# Mega.net
KiCad netlist of a schematic drawn in EAGLE
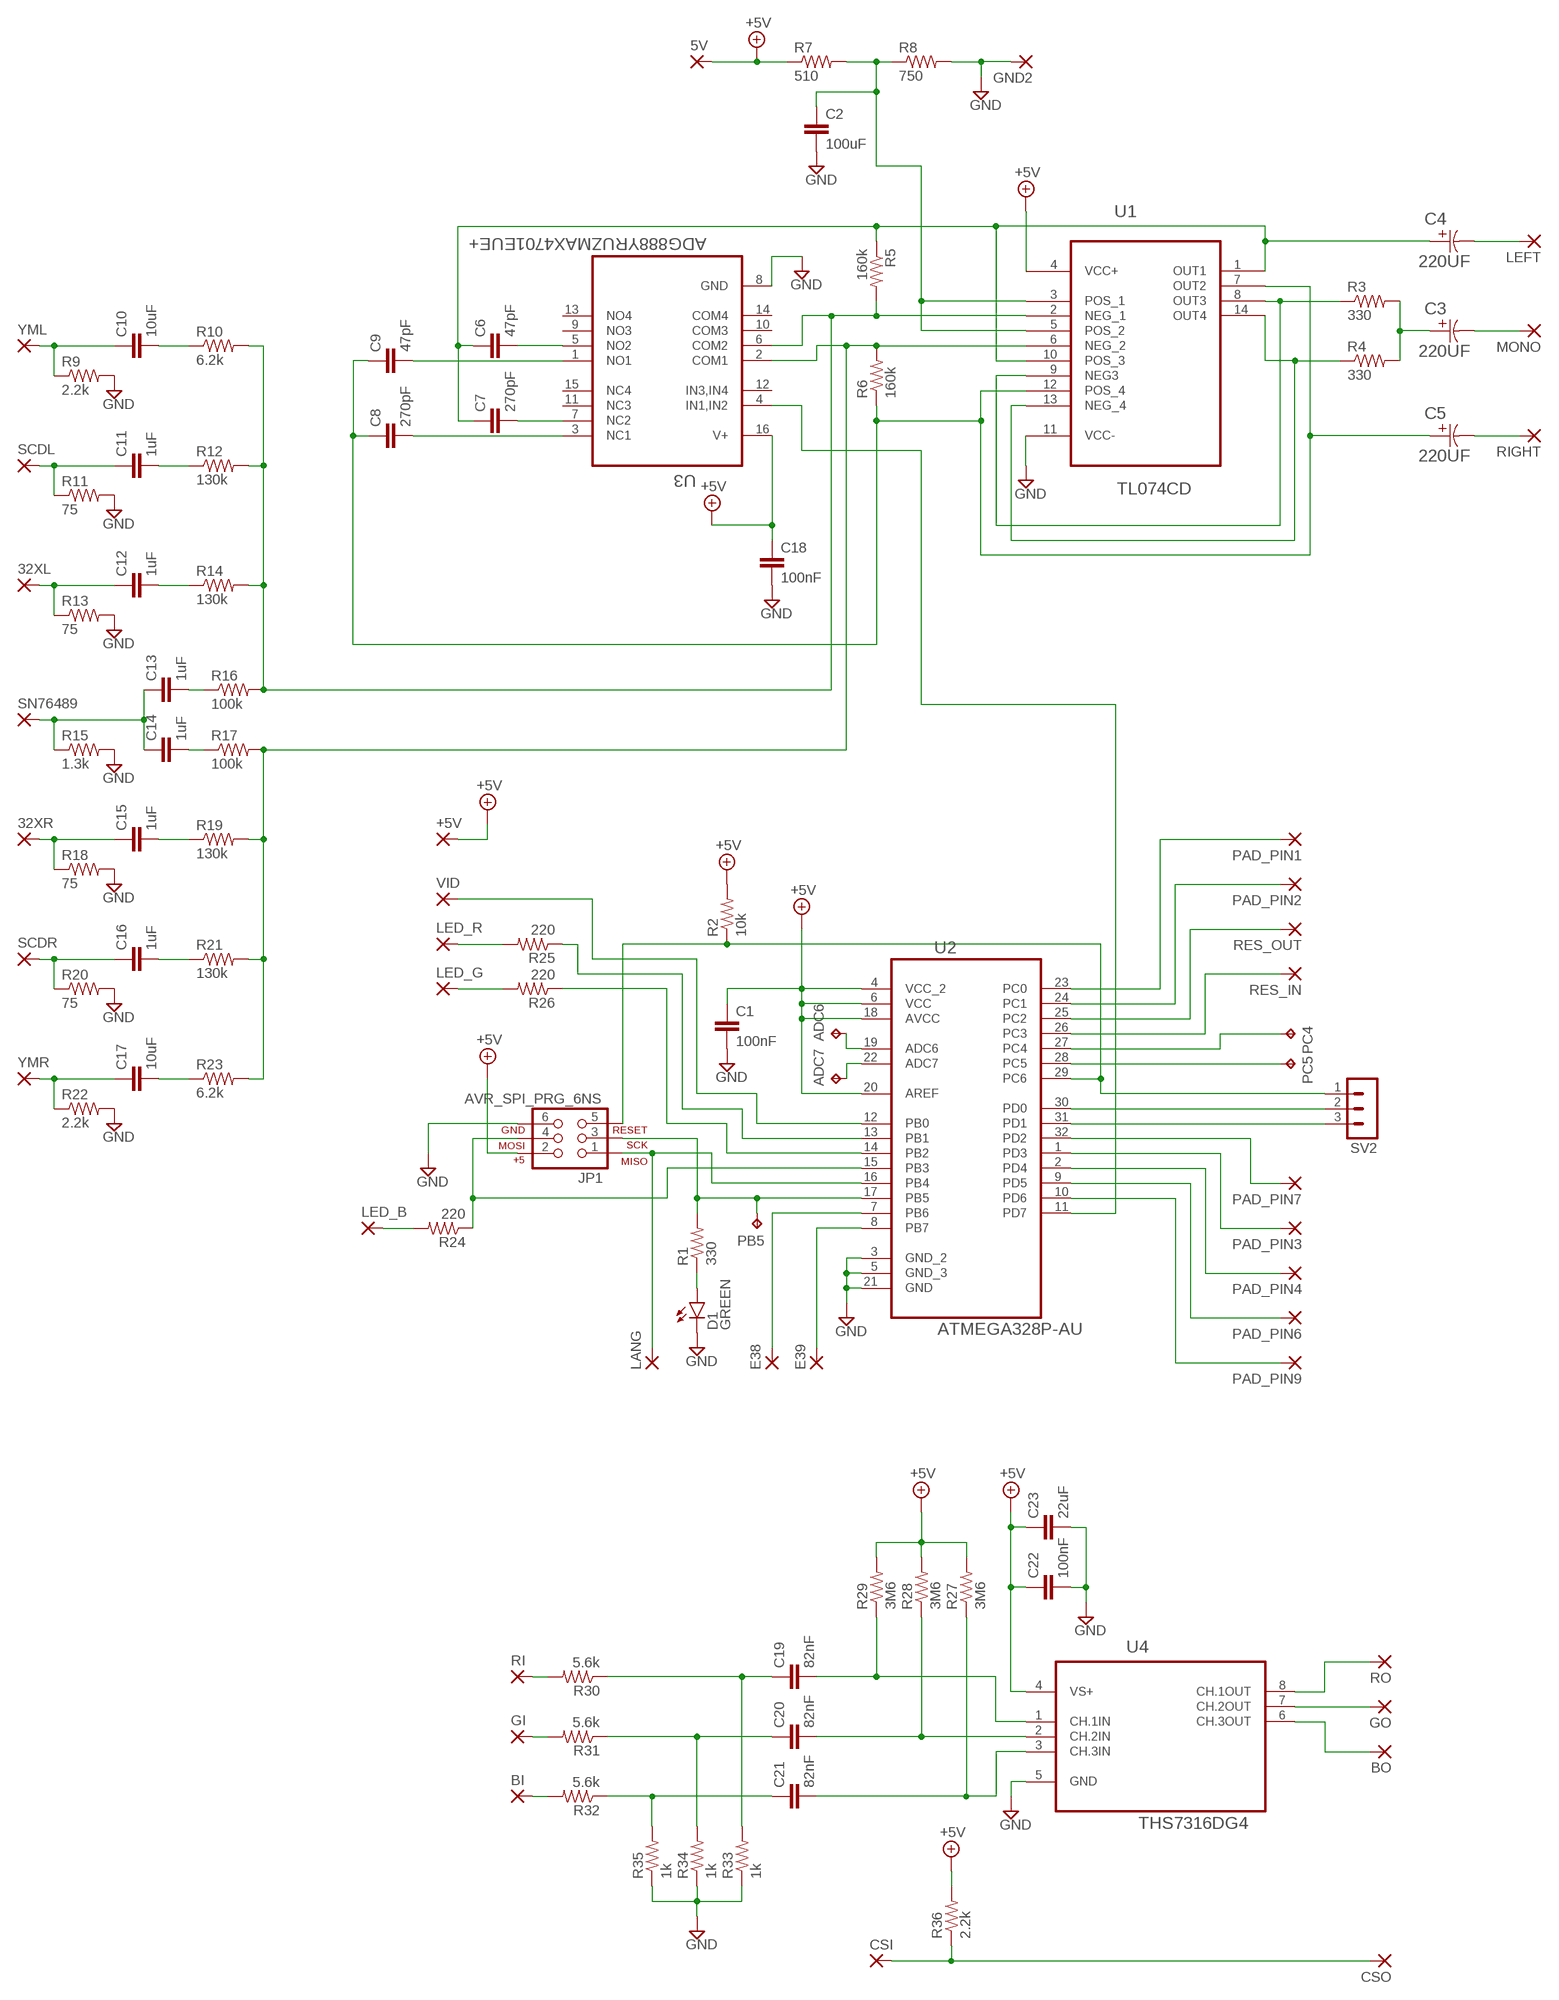
[diagram p0: schematic, sheet 1]

(export (version "E")
  (design (tool "Eeschema 10.0.6"))
  (components
    (comp (ref "+5V")
      (value "SMD2")
      (footprint "eagle-import:SMD1,27-2,54")
      (libsource (lib "eagle-import") (part "SMD2"))
    )
    (comp (ref "5V")
      (value "SMD2")
      (footprint "eagle-import:SMD1,27-2,54")
      (libsource (lib "eagle-import") (part "SMD2"))
    )
    (comp (ref "32XL")
      (value "SMD2")
      (footprint "eagle-import:SMD1,27-2,54")
      (libsource (lib "eagle-import") (part "SMD2"))
    )
    (comp (ref "32XR")
      (value "SMD2")
      (footprint "eagle-import:SMD1,27-2,54")
      (libsource (lib "eagle-import") (part "SMD2"))
    )
    (comp (ref "ADC6")
      (value "TPB1,27")
      (footprint "eagle-import:B1,27")
      (libsource (lib "eagle-import") (part "TPB1,27"))
    )
    (comp (ref "ADC7")
      (value "TPB1,27")
      (footprint "eagle-import:B1,27")
      (libsource (lib "eagle-import") (part "TPB1,27"))
    )
    (comp (ref "BI")
      (value "SMD2")
      (footprint "eagle-import:SMD1,27-2,54")
      (libsource (lib "eagle-import") (part "SMD2"))
    )
    (comp (ref "BO")
      (value "SMD2")
      (footprint "eagle-import:SMD1,27-2,54")
      (libsource (lib "eagle-import") (part "SMD2"))
    )
    (comp (ref "C1")
      (value "100nF")
      (footprint "eagle-import:0805")
      (libsource (lib "eagle-import") (part "CAP0805"))
    )
    (comp (ref "C2")
      (value "100uF")
      (footprint "eagle-import:1206")
      (libsource (lib "eagle-import") (part "CAP1206"))
    )
    (comp (ref "C3")
      (value "220UF")
      (footprint "eagle-import:CAPAE830X650N")
      (fields
        (field (name "MPN") "EEE-FK1C221P")
        (field (name "TOLERANCE") "±20 %")
        (field (name "TOLERANCE_1") "20 %")
      )
      (libsource (lib "eagle-import") (part "EEE--CASE-EFK1C221P"))
    )
    (comp (ref "C4")
      (value "220UF")
      (footprint "eagle-import:CAPAE830X650N")
      (fields
        (field (name "MPN") "EEE-FK1C221P")
        (field (name "TOLERANCE") "±20 %")
        (field (name "TOLERANCE_1") "20 %")
      )
      (libsource (lib "eagle-import") (part "EEE--CASE-EFK1C221P"))
    )
    (comp (ref "C5")
      (value "220UF")
      (footprint "eagle-import:CAPAE830X650N")
      (fields
        (field (name "MPN") "EEE-FK1C221P")
        (field (name "TOLERANCE") "±20 %")
        (field (name "TOLERANCE_1") "20 %")
      )
      (libsource (lib "eagle-import") (part "EEE--CASE-EFK1C221P"))
    )
    (comp (ref "C6")
      (value "47pF")
      (footprint "eagle-import:0805")
      (libsource (lib "eagle-import") (part "CAP0805"))
    )
    (comp (ref "C7")
      (value "270pF")
      (footprint "eagle-import:0805")
      (libsource (lib "eagle-import") (part "CAP0805"))
    )
    (comp (ref "C8")
      (value "270pF")
      (footprint "eagle-import:0805")
      (libsource (lib "eagle-import") (part "CAP0805"))
    )
    (comp (ref "C9")
      (value "47pF")
      (footprint "eagle-import:0805")
      (libsource (lib "eagle-import") (part "CAP0805"))
    )
    (comp (ref "C10")
      (value "10uF")
      (footprint "eagle-import:0805")
      (libsource (lib "eagle-import") (part "CAP0805"))
    )
    (comp (ref "C11")
      (value "1uF")
      (footprint "eagle-import:0805")
      (libsource (lib "eagle-import") (part "CAP0805"))
    )
    (comp (ref "C12")
      (value "1uF")
      (footprint "eagle-import:0805")
      (libsource (lib "eagle-import") (part "CAP0805"))
    )
    (comp (ref "C13")
      (value "1uF")
      (footprint "eagle-import:0805")
      (libsource (lib "eagle-import") (part "CAP0805"))
    )
    (comp (ref "C14")
      (value "1uF")
      (footprint "eagle-import:0805")
      (libsource (lib "eagle-import") (part "CAP0805"))
    )
    (comp (ref "C15")
      (value "1uF")
      (footprint "eagle-import:0805")
      (libsource (lib "eagle-import") (part "CAP0805"))
    )
    (comp (ref "C16")
      (value "1uF")
      (footprint "eagle-import:0805")
      (libsource (lib "eagle-import") (part "CAP0805"))
    )
    (comp (ref "C17")
      (value "10uF")
      (footprint "eagle-import:0805")
      (libsource (lib "eagle-import") (part "CAP0805"))
    )
    (comp (ref "C18")
      (value "100nF")
      (footprint "eagle-import:0805")
      (libsource (lib "eagle-import") (part "CAP0805"))
    )
    (comp (ref "C19")
      (value "82nF")
      (footprint "eagle-import:0805")
      (libsource (lib "eagle-import") (part "CAP0805"))
    )
    (comp (ref "C20")
      (value "82nF")
      (footprint "eagle-import:0805")
      (libsource (lib "eagle-import") (part "CAP0805"))
    )
    (comp (ref "C21")
      (value "82nF")
      (footprint "eagle-import:0805")
      (libsource (lib "eagle-import") (part "CAP0805"))
    )
    (comp (ref "C22")
      (value "100nF")
      (footprint "eagle-import:0805")
      (libsource (lib "eagle-import") (part "CAP0805"))
    )
    (comp (ref "C23")
      (value "22uF")
      (footprint "eagle-import:0805")
      (libsource (lib "eagle-import") (part "CAP0805"))
    )
    (comp (ref "CSI")
      (value "SMD2")
      (footprint "eagle-import:SMD1,27-2,54")
      (libsource (lib "eagle-import") (part "SMD2"))
    )
    (comp (ref "CSO")
      (value "SMD2")
      (footprint "eagle-import:SMD1,27-2,54")
      (libsource (lib "eagle-import") (part "SMD2"))
    )
    (comp (ref "D1")
      (value "GREEN")
      (footprint "eagle-import:LED-1206")
      (libsource (lib "eagle-import") (part "LED1206"))
    )
    (comp (ref "E38")
      (value "SMD2")
      (footprint "eagle-import:SMD1,27-2,54")
      (libsource (lib "eagle-import") (part "SMD2"))
    )
    (comp (ref "E39")
      (value "SMD2")
      (footprint "eagle-import:SMD1,27-2,54")
      (libsource (lib "eagle-import") (part "SMD2"))
    )
    (comp (ref "GI")
      (value "SMD2")
      (footprint "eagle-import:SMD1,27-2,54")
      (libsource (lib "eagle-import") (part "SMD2"))
    )
    (comp (ref "GND2")
      (value "SMD2")
      (footprint "eagle-import:SMD1,27-2,54")
      (libsource (lib "eagle-import") (part "SMD2"))
    )
    (comp (ref "GO")
      (value "SMD2")
      (footprint "eagle-import:SMD1,27-2,54")
      (libsource (lib "eagle-import") (part "SMD2"))
    )
    (comp (ref "JP1")
      (value "AVR_SPI_PRG_6NS")
      (footprint "eagle-import:2X3-NS")
      (libsource (lib "eagle-import") (part "AVR_SPI_PRG_6NS"))
    )
    (comp (ref "LANG")
      (value "SMD2")
      (footprint "eagle-import:SMD1,27-2,54")
      (libsource (lib "eagle-import") (part "SMD2"))
    )
    (comp (ref "LED_B")
      (value "SMD2")
      (footprint "eagle-import:SMD1,27-2,54")
      (libsource (lib "eagle-import") (part "SMD2"))
    )
    (comp (ref "LED_G")
      (value "SMD2")
      (footprint "eagle-import:SMD1,27-2,54")
      (libsource (lib "eagle-import") (part "SMD2"))
    )
    (comp (ref "LED_R")
      (value "SMD2")
      (footprint "eagle-import:SMD1,27-2,54")
      (libsource (lib "eagle-import") (part "SMD2"))
    )
    (comp (ref "LEFT")
      (value "SMD2")
      (footprint "eagle-import:SMD1,27-2,54")
      (libsource (lib "eagle-import") (part "SMD2"))
    )
    (comp (ref "MONO")
      (value "SMD2")
      (footprint "eagle-import:SMD1,27-2,54")
      (libsource (lib "eagle-import") (part "SMD2"))
    )
    (comp (ref "PAD_PIN1")
      (value "SMD2")
      (footprint "eagle-import:SMD1,27-2,54")
      (libsource (lib "eagle-import") (part "SMD2"))
    )
    (comp (ref "PAD_PIN2")
      (value "SMD2")
      (footprint "eagle-import:SMD1,27-2,54")
      (libsource (lib "eagle-import") (part "SMD2"))
    )
    (comp (ref "PAD_PIN3")
      (value "SMD2")
      (footprint "eagle-import:SMD1,27-2,54")
      (libsource (lib "eagle-import") (part "SMD2"))
    )
    (comp (ref "PAD_PIN4")
      (value "SMD2")
      (footprint "eagle-import:SMD1,27-2,54")
      (libsource (lib "eagle-import") (part "SMD2"))
    )
    (comp (ref "PAD_PIN6")
      (value "SMD2")
      (footprint "eagle-import:SMD1,27-2,54")
      (libsource (lib "eagle-import") (part "SMD2"))
    )
    (comp (ref "PAD_PIN7")
      (value "SMD2")
      (footprint "eagle-import:SMD1,27-2,54")
      (libsource (lib "eagle-import") (part "SMD2"))
    )
    (comp (ref "PAD_PIN9")
      (value "SMD2")
      (footprint "eagle-import:SMD1,27-2,54")
      (libsource (lib "eagle-import") (part "SMD2"))
    )
    (comp (ref "PB5")
      (value "TPB1,27")
      (footprint "eagle-import:B1,27")
      (libsource (lib "eagle-import") (part "TPB1,27"))
    )
    (comp (ref "PC4")
      (value "TPB1,27")
      (footprint "eagle-import:B1,27")
      (libsource (lib "eagle-import") (part "TPB1,27"))
    )
    (comp (ref "PC5")
      (value "TPB1,27")
      (footprint "eagle-import:B1,27")
      (libsource (lib "eagle-import") (part "TPB1,27"))
    )
    (comp (ref "R1")
      (value "330")
      (footprint "eagle-import:0805")
      (libsource (lib "eagle-import") (part "RESISTOR0805-RES"))
    )
    (comp (ref "R2")
      (value "10k")
      (footprint "eagle-import:0805")
      (libsource (lib "eagle-import") (part "RESISTOR0805-RES"))
    )
    (comp (ref "R3")
      (value "330")
      (footprint "eagle-import:0805")
      (libsource (lib "eagle-import") (part "RESISTOR0805-RES"))
    )
    (comp (ref "R4")
      (value "330")
      (footprint "eagle-import:0805")
      (libsource (lib "eagle-import") (part "RESISTOR0805-RES"))
    )
    (comp (ref "R5")
      (value "160k")
      (footprint "eagle-import:0805")
      (libsource (lib "eagle-import") (part "RESISTOR0805-RES"))
    )
    (comp (ref "R6")
      (value "160k")
      (footprint "eagle-import:0805")
      (libsource (lib "eagle-import") (part "RESISTOR0805-RES"))
    )
    (comp (ref "R7")
      (value "510")
      (footprint "eagle-import:0805")
      (libsource (lib "eagle-import") (part "RESISTOR0805-RES"))
    )
    (comp (ref "R8")
      (value "750")
      (footprint "eagle-import:0805")
      (libsource (lib "eagle-import") (part "RESISTOR0805-RES"))
    )
    (comp (ref "R9")
      (value "2.2k")
      (footprint "eagle-import:0805")
      (libsource (lib "eagle-import") (part "RESISTOR0805-RES"))
    )
    (comp (ref "R10")
      (value "6.2k")
      (footprint "eagle-import:0805")
      (libsource (lib "eagle-import") (part "RESISTOR0805-RES"))
    )
    (comp (ref "R11")
      (value "75")
      (footprint "eagle-import:0805")
      (libsource (lib "eagle-import") (part "RESISTOR0805-RES"))
    )
    (comp (ref "R12")
      (value "130k")
      (footprint "eagle-import:0805")
      (libsource (lib "eagle-import") (part "RESISTOR0805-RES"))
    )
    (comp (ref "R13")
      (value "75")
      (footprint "eagle-import:0805")
      (libsource (lib "eagle-import") (part "RESISTOR0805-RES"))
    )
    (comp (ref "R14")
      (value "130k")
      (footprint "eagle-import:0805")
      (libsource (lib "eagle-import") (part "RESISTOR0805-RES"))
    )
    (comp (ref "R15")
      (value "1.3k")
      (footprint "eagle-import:0805")
      (libsource (lib "eagle-import") (part "RESISTOR0805-RES"))
    )
    (comp (ref "R16")
      (value "100k")
      (footprint "eagle-import:0805")
      (libsource (lib "eagle-import") (part "RESISTOR0805-RES"))
    )
    (comp (ref "R17")
      (value "100k")
      (footprint "eagle-import:0805")
      (libsource (lib "eagle-import") (part "RESISTOR0805-RES"))
    )
    (comp (ref "R18")
      (value "75")
      (footprint "eagle-import:0805")
      (libsource (lib "eagle-import") (part "RESISTOR0805-RES"))
    )
    (comp (ref "R19")
      (value "130k")
      (footprint "eagle-import:0805")
      (libsource (lib "eagle-import") (part "RESISTOR0805-RES"))
    )
    (comp (ref "R20")
      (value "75")
      (footprint "eagle-import:0805")
      (libsource (lib "eagle-import") (part "RESISTOR0805-RES"))
    )
    (comp (ref "R21")
      (value "130k")
      (footprint "eagle-import:0805")
      (libsource (lib "eagle-import") (part "RESISTOR0805-RES"))
    )
    (comp (ref "R22")
      (value "2.2k")
      (footprint "eagle-import:0805")
      (libsource (lib "eagle-import") (part "RESISTOR0805-RES"))
    )
    (comp (ref "R23")
      (value "6.2k")
      (footprint "eagle-import:0805")
      (libsource (lib "eagle-import") (part "RESISTOR0805-RES"))
    )
    (comp (ref "R24")
      (value "220")
      (footprint "eagle-import:0805")
      (libsource (lib "eagle-import") (part "RESISTOR0805-RES"))
    )
    (comp (ref "R25")
      (value "220")
      (footprint "eagle-import:0805")
      (libsource (lib "eagle-import") (part "RESISTOR0805-RES"))
    )
    (comp (ref "R26")
      (value "220")
      (footprint "eagle-import:0805")
      (libsource (lib "eagle-import") (part "RESISTOR0805-RES"))
    )
    (comp (ref "R27")
      (value "3M6")
      (footprint "eagle-import:0805")
      (libsource (lib "eagle-import") (part "RESISTOR0805-RES"))
    )
    (comp (ref "R28")
      (value "3M6")
      (footprint "eagle-import:0805")
      (libsource (lib "eagle-import") (part "RESISTOR0805-RES"))
    )
    (comp (ref "R29")
      (value "3M6")
      (footprint "eagle-import:0805")
      (libsource (lib "eagle-import") (part "RESISTOR0805-RES"))
    )
    (comp (ref "R30")
      (value "5.6k")
      (footprint "eagle-import:0805")
      (libsource (lib "eagle-import") (part "RESISTOR0805-RES"))
    )
    (comp (ref "R31")
      (value "5.6k")
      (footprint "eagle-import:0805")
      (libsource (lib "eagle-import") (part "RESISTOR0805-RES"))
    )
    (comp (ref "R32")
      (value "5.6k")
      (footprint "eagle-import:0805")
      (libsource (lib "eagle-import") (part "RESISTOR0805-RES"))
    )
    (comp (ref "R33")
      (value "1k")
      (footprint "eagle-import:0805")
      (libsource (lib "eagle-import") (part "RESISTOR0805-RES"))
    )
    (comp (ref "R34")
      (value "1k")
      (footprint "eagle-import:0805")
      (libsource (lib "eagle-import") (part "RESISTOR0805-RES"))
    )
    (comp (ref "R35")
      (value "1k")
      (footprint "eagle-import:0805")
      (libsource (lib "eagle-import") (part "RESISTOR0805-RES"))
    )
    (comp (ref "R36")
      (value "2.2k")
      (footprint "eagle-import:0805")
      (libsource (lib "eagle-import") (part "RESISTOR0805-RES"))
    )
    (comp (ref "RES_IN")
      (value "SMD2")
      (footprint "eagle-import:SMD1,27-2,54")
      (libsource (lib "eagle-import") (part "SMD2"))
    )
    (comp (ref "RES_OUT")
      (value "SMD2")
      (footprint "eagle-import:SMD1,27-2,54")
      (libsource (lib "eagle-import") (part "SMD2"))
    )
    (comp (ref "RI")
      (value "SMD2")
      (footprint "eagle-import:SMD1,27-2,54")
      (libsource (lib "eagle-import") (part "SMD2"))
    )
    (comp (ref "RIGHT")
      (value "SMD2")
      (footprint "eagle-import:SMD1,27-2,54")
      (libsource (lib "eagle-import") (part "SMD2"))
    )
    (comp (ref "RO")
      (value "SMD2")
      (footprint "eagle-import:SMD1,27-2,54")
      (libsource (lib "eagle-import") (part "SMD2"))
    )
    (comp (ref "SCDL")
      (value "SMD2")
      (footprint "eagle-import:SMD1,27-2,54")
      (libsource (lib "eagle-import") (part "SMD2"))
    )
    (comp (ref "SCDR")
      (value "SMD2")
      (footprint "eagle-import:SMD1,27-2,54")
      (libsource (lib "eagle-import") (part "SMD2"))
    )
    (comp (ref "SN76489")
      (value "SMD2")
      (footprint "eagle-import:SMD1,27-2,54")
      (libsource (lib "eagle-import") (part "SMD2"))
    )
    (comp (ref "SV2")
      (value "MA03-1")
      (footprint "eagle-import:MA03-1")
      (libsource (lib "eagle-import") (part "MA03-1"))
    )
    (comp (ref "U1")
      (value "TL074CD")
      (footprint "eagle-import:SOIC127P600X175-14N")
      (libsource (lib "eagle-import") (part "TL074CD"))
    )
    (comp (ref "U2")
      (value "ATMEGA328P-AU")
      (footprint "eagle-import:QFP80P900X900X120-32N")
      (libsource (lib "eagle-import") (part "ATMEGA328P-AU"))
    )
    (comp (ref "U3")
      (value "ADG888YRUZMAX4701EUE+")
      (footprint "eagle-import:SOP65P640X120-16N")
      (libsource (lib "eagle-import") (part "ADG888YRUZMAX4701EUE+"))
    )
    (comp (ref "U4")
      (value "THS7316DG4")
      (footprint "eagle-import:SOIC127P600X175-8N")
      (libsource (lib "eagle-import") (part "THS7316DG4"))
    )
    (comp (ref "VID")
      (value "SMD2")
      (footprint "eagle-import:SMD1,27-2,54")
      (libsource (lib "eagle-import") (part "SMD2"))
    )
    (comp (ref "YML")
      (value "SMD2")
      (footprint "eagle-import:SMD1,27-2,54")
      (libsource (lib "eagle-import") (part "SMD2"))
    )
    (comp (ref "YMR")
      (value "SMD2")
      (footprint "eagle-import:SMD1,27-2,54")
      (libsource (lib "eagle-import") (part "SMD2"))
    )
  )
  (nets
    (net (code "1") (name "+5V") (class "Default")
      (node (ref "+5V") (pin "1") (pinfunction "P_1") (pintype "passive"))
      (node (ref "5V") (pin "1") (pinfunction "P_1") (pintype "passive"))
      (node (ref "C1") (pin "1") (pinfunction "1_1") (pintype "passive"))
      (node (ref "C18") (pin "1") (pinfunction "1_1") (pintype "passive"))
      (node (ref "C22") (pin "1") (pinfunction "1_1") (pintype "passive"))
      (node (ref "C23") (pin "1") (pinfunction "1_1") (pintype "passive"))
      (node (ref "JP1") (pin "2") (pinfunction "2_2") (pintype "passive"))
      (node (ref "R2") (pin "2") (pinfunction "2_2") (pintype "passive"))
      (node (ref "R27") (pin "2") (pinfunction "2_2") (pintype "passive"))
      (node (ref "R28") (pin "2") (pinfunction "2_2") (pintype "passive"))
      (node (ref "R29") (pin "2") (pinfunction "2_2") (pintype "passive"))
      (node (ref "R36") (pin "2") (pinfunction "2_2") (pintype "passive"))
      (node (ref "R7") (pin "1") (pinfunction "1_1") (pintype "passive"))
      (node (ref "U1") (pin "4") (pinfunction "VCC+_4") (pintype "power_in"))
      (node (ref "U2") (pin "18") (pinfunction "AVCC_18") (pintype "power_in"))
      (node (ref "U2") (pin "20") (pinfunction "AREF_20") (pintype "input"))
      (node (ref "U2") (pin "4") (pinfunction "VCC_2_4") (pintype "power_in"))
      (node (ref "U2") (pin "6") (pinfunction "VCC_6") (pintype "power_in"))
      (node (ref "U3") (pin "16") (pinfunction "V+_16") (pintype "power_in"))
      (node (ref "U4") (pin "4") (pinfunction "VS+_4") (pintype "power_in"))
    )
    (net (code "2") (name "GND") (class "Default")
      (node (ref "C1") (pin "2") (pinfunction "2_2") (pintype "passive"))
      (node (ref "C18") (pin "2") (pinfunction "2_2") (pintype "passive"))
      (node (ref "C2") (pin "2") (pinfunction "2_2") (pintype "passive"))
      (node (ref "C22") (pin "2") (pinfunction "2_2") (pintype "passive"))
      (node (ref "C23") (pin "2") (pinfunction "2_2") (pintype "passive"))
      (node (ref "D1") (pin "C") (pinfunction "C_C") (pintype "passive"))
      (node (ref "GND2") (pin "1") (pinfunction "P_1") (pintype "passive"))
      (node (ref "JP1") (pin "6") (pinfunction "6_6") (pintype "passive"))
      (node (ref "R11") (pin "2") (pinfunction "2_2") (pintype "passive"))
      (node (ref "R13") (pin "2") (pinfunction "2_2") (pintype "passive"))
      (node (ref "R15") (pin "2") (pinfunction "2_2") (pintype "passive"))
      (node (ref "R18") (pin "2") (pinfunction "2_2") (pintype "passive"))
      (node (ref "R20") (pin "2") (pinfunction "2_2") (pintype "passive"))
      (node (ref "R22") (pin "2") (pinfunction "2_2") (pintype "passive"))
      (node (ref "R33") (pin "1") (pinfunction "1_1") (pintype "passive"))
      (node (ref "R34") (pin "1") (pinfunction "1_1") (pintype "passive"))
      (node (ref "R35") (pin "1") (pinfunction "1_1") (pintype "passive"))
      (node (ref "R8") (pin "2") (pinfunction "2_2") (pintype "passive"))
      (node (ref "R9") (pin "2") (pinfunction "2_2") (pintype "passive"))
      (node (ref "U1") (pin "11") (pinfunction "VCC-_11") (pintype "power_in"))
      (node (ref "U2") (pin "21") (pinfunction "GND_21") (pintype "passive"))
      (node (ref "U2") (pin "3") (pinfunction "GND_2_3") (pintype "passive"))
      (node (ref "U2") (pin "5") (pinfunction "GND_3_5") (pintype "passive"))
      (node (ref "U3") (pin "8") (pinfunction "GND_8") (pintype "passive"))
      (node (ref "U4") (pin "5") (pinfunction "GND_5") (pintype "passive"))
    )
    (net (code "3") (name "Net-(32XL-P)") (class "Default")
      (node (ref "32XL") (pin "1") (pinfunction "P_1") (pintype "passive"))
      (node (ref "C12") (pin "1") (pinfunction "1_1") (pintype "passive"))
      (node (ref "R13") (pin "1") (pinfunction "1_1") (pintype "passive"))
    )
    (net (code "4") (name "Net-(32XR-P)") (class "Default")
      (node (ref "32XR") (pin "1") (pinfunction "P_1") (pintype "passive"))
      (node (ref "C15") (pin "1") (pinfunction "1_1") (pintype "passive"))
      (node (ref "R18") (pin "1") (pinfunction "1_1") (pintype "passive"))
    )
    (net (code "5") (name "Net-(BI-P)") (class "Default")
      (node (ref "BI") (pin "1") (pinfunction "P_1") (pintype "passive"))
      (node (ref "R32") (pin "2") (pinfunction "2_2") (pintype "passive"))
    )
    (net (code "6") (name "Net-(BO-P)") (class "Default")
      (node (ref "BO") (pin "1") (pinfunction "P_1") (pintype "passive"))
      (node (ref "U4") (pin "6") (pinfunction "CH.3OUT_6") (pintype "output"))
    )
    (net (code "7") (name "Net-(C3-Pad1)") (class "Default")
      (node (ref "C3") (pin "1") (pinfunction "1_1") (pintype "passive"))
      (node (ref "R3") (pin "2") (pinfunction "2_2") (pintype "passive"))
      (node (ref "R4") (pin "2") (pinfunction "2_2") (pintype "passive"))
    )
    (net (code "8") (name "Net-(C10-Pad2)") (class "Default")
      (node (ref "C10") (pin "2") (pinfunction "2_2") (pintype "passive"))
      (node (ref "R10") (pin "1") (pinfunction "1_1") (pintype "passive"))
    )
    (net (code "9") (name "Net-(C11-Pad2)") (class "Default")
      (node (ref "C11") (pin "2") (pinfunction "2_2") (pintype "passive"))
      (node (ref "R12") (pin "1") (pinfunction "1_1") (pintype "passive"))
    )
    (net (code "10") (name "Net-(C12-Pad2)") (class "Default")
      (node (ref "C12") (pin "2") (pinfunction "2_2") (pintype "passive"))
      (node (ref "R14") (pin "1") (pinfunction "1_1") (pintype "passive"))
    )
    (net (code "11") (name "Net-(C13-Pad2)") (class "Default")
      (node (ref "C13") (pin "2") (pinfunction "2_2") (pintype "passive"))
      (node (ref "R16") (pin "1") (pinfunction "1_1") (pintype "passive"))
    )
    (net (code "12") (name "Net-(C14-Pad2)") (class "Default")
      (node (ref "C14") (pin "2") (pinfunction "2_2") (pintype "passive"))
      (node (ref "R17") (pin "1") (pinfunction "1_1") (pintype "passive"))
    )
    (net (code "13") (name "Net-(C15-Pad2)") (class "Default")
      (node (ref "C15") (pin "2") (pinfunction "2_2") (pintype "passive"))
      (node (ref "R19") (pin "1") (pinfunction "1_1") (pintype "passive"))
    )
    (net (code "14") (name "Net-(C16-Pad2)") (class "Default")
      (node (ref "C16") (pin "2") (pinfunction "2_2") (pintype "passive"))
      (node (ref "R21") (pin "1") (pinfunction "1_1") (pintype "passive"))
    )
    (net (code "15") (name "Net-(C17-Pad2)") (class "Default")
      (node (ref "C17") (pin "2") (pinfunction "2_2") (pintype "passive"))
      (node (ref "R23") (pin "1") (pinfunction "1_1") (pintype "passive"))
    )
    (net (code "16") (name "Net-(C19-Pad1)") (class "Default")
      (node (ref "C19") (pin "1") (pinfunction "1_1") (pintype "passive"))
      (node (ref "R30") (pin "1") (pinfunction "1_1") (pintype "passive"))
      (node (ref "R33") (pin "2") (pinfunction "2_2") (pintype "passive"))
    )
    (net (code "17") (name "Net-(C20-Pad1)") (class "Default")
      (node (ref "C20") (pin "1") (pinfunction "1_1") (pintype "passive"))
      (node (ref "R31") (pin "1") (pinfunction "1_1") (pintype "passive"))
      (node (ref "R34") (pin "2") (pinfunction "2_2") (pintype "passive"))
    )
    (net (code "18") (name "Net-(C21-Pad1)") (class "Default")
      (node (ref "C21") (pin "1") (pinfunction "1_1") (pintype "passive"))
      (node (ref "R32") (pin "1") (pinfunction "1_1") (pintype "passive"))
      (node (ref "R35") (pin "2") (pinfunction "2_2") (pintype "passive"))
    )
    (net (code "19") (name "Net-(CSI-P)") (class "Default")
      (node (ref "CSI") (pin "1") (pinfunction "P_1") (pintype "passive"))
      (node (ref "CSO") (pin "1") (pinfunction "P_1") (pintype "passive"))
      (node (ref "R36") (pin "1") (pinfunction "1_1") (pintype "passive"))
    )
    (net (code "20") (name "Net-(D1-PadA)") (class "Default")
      (node (ref "D1") (pin "A") (pinfunction "A_A") (pintype "passive"))
      (node (ref "R1") (pin "1") (pinfunction "1_1") (pintype "passive"))
    )
    (net (code "21") (name "Net-(E38-P)") (class "Default")
      (node (ref "E38") (pin "1") (pinfunction "P_1") (pintype "passive"))
      (node (ref "U2") (pin "7") (pinfunction "PB6_7") (pintype "bidirectional"))
    )
    (net (code "22") (name "Net-(E39-P)") (class "Default")
      (node (ref "E39") (pin "1") (pinfunction "P_1") (pintype "passive"))
      (node (ref "U2") (pin "8") (pinfunction "PB7_8") (pintype "bidirectional"))
    )
    (net (code "23") (name "Net-(GI-P)") (class "Default")
      (node (ref "GI") (pin "1") (pinfunction "P_1") (pintype "passive"))
      (node (ref "R31") (pin "2") (pinfunction "2_2") (pintype "passive"))
    )
    (net (code "24") (name "Net-(GO-P)") (class "Default")
      (node (ref "GO") (pin "1") (pinfunction "P_1") (pintype "passive"))
      (node (ref "U4") (pin "7") (pinfunction "CH.2OUT_7") (pintype "output"))
    )
    (net (code "25") (name "Net-(LANG-P)") (class "Default")
      (node (ref "JP1") (pin "1") (pinfunction "1_1") (pintype "passive"))
      (node (ref "LANG") (pin "1") (pinfunction "P_1") (pintype "passive"))
      (node (ref "U2") (pin "16") (pinfunction "PB4_16") (pintype "bidirectional"))
    )
    (net (code "26") (name "Net-(LED_B-P)") (class "Default")
      (node (ref "LED_B") (pin "1") (pinfunction "P_1") (pintype "passive"))
      (node (ref "R24") (pin "2") (pinfunction "2_2") (pintype "passive"))
    )
    (net (code "27") (name "Net-(LED_G-P)") (class "Default")
      (node (ref "LED_G") (pin "1") (pinfunction "P_1") (pintype "passive"))
      (node (ref "R26") (pin "2") (pinfunction "2_2") (pintype "passive"))
    )
    (net (code "28") (name "Net-(LED_R-P)") (class "Default")
      (node (ref "LED_R") (pin "1") (pinfunction "P_1") (pintype "passive"))
      (node (ref "R25") (pin "2") (pinfunction "2_2") (pintype "passive"))
    )
    (net (code "29") (name "Net-(LEFT-P)") (class "Default")
      (node (ref "C4") (pin "2") (pinfunction "2_2") (pintype "passive"))
      (node (ref "LEFT") (pin "1") (pinfunction "P_1") (pintype "passive"))
    )
    (net (code "30") (name "Net-(MONO-P)") (class "Default")
      (node (ref "C3") (pin "2") (pinfunction "2_2") (pintype "passive"))
      (node (ref "MONO") (pin "1") (pinfunction "P_1") (pintype "passive"))
    )
    (net (code "31") (name "Net-(PAD_PIN1-P)") (class "Default")
      (node (ref "PAD_PIN1") (pin "1") (pinfunction "P_1") (pintype "passive"))
      (node (ref "U2") (pin "23") (pinfunction "PC0_23") (pintype "bidirectional"))
    )
    (net (code "32") (name "Net-(PAD_PIN2-P)") (class "Default")
      (node (ref "PAD_PIN2") (pin "1") (pinfunction "P_1") (pintype "passive"))
      (node (ref "U2") (pin "24") (pinfunction "PC1_24") (pintype "bidirectional"))
    )
    (net (code "33") (name "Net-(PAD_PIN3-P)") (class "Default")
      (node (ref "PAD_PIN3") (pin "1") (pinfunction "P_1") (pintype "passive"))
      (node (ref "U2") (pin "1") (pinfunction "PD3_1") (pintype "bidirectional"))
    )
    (net (code "34") (name "Net-(PAD_PIN4-P)") (class "Default")
      (node (ref "PAD_PIN4") (pin "1") (pinfunction "P_1") (pintype "passive"))
      (node (ref "U2") (pin "2") (pinfunction "PD4_2") (pintype "bidirectional"))
    )
    (net (code "35") (name "Net-(PAD_PIN6-P)") (class "Default")
      (node (ref "PAD_PIN6") (pin "1") (pinfunction "P_1") (pintype "passive"))
      (node (ref "U2") (pin "9") (pinfunction "PD5_9") (pintype "bidirectional"))
    )
    (net (code "36") (name "Net-(PAD_PIN7-P)") (class "Default")
      (node (ref "PAD_PIN7") (pin "1") (pinfunction "P_1") (pintype "passive"))
      (node (ref "U2") (pin "32") (pinfunction "PD2_32") (pintype "bidirectional"))
    )
    (net (code "37") (name "Net-(PAD_PIN9-P)") (class "Default")
      (node (ref "PAD_PIN9") (pin "1") (pinfunction "P_1") (pintype "passive"))
      (node (ref "U2") (pin "10") (pinfunction "PD6_10") (pintype "bidirectional"))
    )
    (net (code "38") (name "Net-(RES_IN-P)") (class "Default")
      (node (ref "RES_IN") (pin "1") (pinfunction "P_1") (pintype "passive"))
      (node (ref "U2") (pin "26") (pinfunction "PC3_26") (pintype "bidirectional"))
    )
    (net (code "39") (name "Net-(RES_OUT-P)") (class "Default")
      (node (ref "RES_OUT") (pin "1") (pinfunction "P_1") (pintype "passive"))
      (node (ref "U2") (pin "25") (pinfunction "PC2_25") (pintype "bidirectional"))
    )
    (net (code "40") (name "Net-(RI-P)") (class "Default")
      (node (ref "R30") (pin "2") (pinfunction "2_2") (pintype "passive"))
      (node (ref "RI") (pin "1") (pinfunction "P_1") (pintype "passive"))
    )
    (net (code "41") (name "Net-(RIGHT-P)") (class "Default")
      (node (ref "C5") (pin "2") (pinfunction "2_2") (pintype "passive"))
      (node (ref "RIGHT") (pin "1") (pinfunction "P_1") (pintype "passive"))
    )
    (net (code "42") (name "Net-(RO-P)") (class "Default")
      (node (ref "RO") (pin "1") (pinfunction "P_1") (pintype "passive"))
      (node (ref "U4") (pin "8") (pinfunction "CH.1OUT_8") (pintype "output"))
    )
    (net (code "43") (name "Net-(SCDL-P)") (class "Default")
      (node (ref "C11") (pin "1") (pinfunction "1_1") (pintype "passive"))
      (node (ref "R11") (pin "1") (pinfunction "1_1") (pintype "passive"))
      (node (ref "SCDL") (pin "1") (pinfunction "P_1") (pintype "passive"))
    )
    (net (code "44") (name "Net-(SCDR-P)") (class "Default")
      (node (ref "C16") (pin "1") (pinfunction "1_1") (pintype "passive"))
      (node (ref "R20") (pin "1") (pinfunction "1_1") (pintype "passive"))
      (node (ref "SCDR") (pin "1") (pinfunction "P_1") (pintype "passive"))
    )
    (net (code "45") (name "Net-(SN76489-P)") (class "Default")
      (node (ref "C13") (pin "1") (pinfunction "1_1") (pintype "passive"))
      (node (ref "C14") (pin "1") (pinfunction "1_1") (pintype "passive"))
      (node (ref "R15") (pin "1") (pinfunction "1_1") (pintype "passive"))
      (node (ref "SN76489") (pin "1") (pinfunction "P_1") (pintype "passive"))
    )
    (net (code "46") (name "Net-(U1-NEG3)") (class "Default")
      (node (ref "R3") (pin "1") (pinfunction "1_1") (pintype "passive"))
      (node (ref "U1") (pin "8") (pinfunction "OUT3_8") (pintype "output"))
      (node (ref "U1") (pin "9") (pinfunction "NEG3_9") (pintype "input"))
    )
    (net (code "47") (name "Net-(U1-NEG_1)") (class "Default")
      (node (ref "R10") (pin "2") (pinfunction "2_2") (pintype "passive"))
      (node (ref "R12") (pin "2") (pinfunction "2_2") (pintype "passive"))
      (node (ref "R14") (pin "2") (pinfunction "2_2") (pintype "passive"))
      (node (ref "R16") (pin "2") (pinfunction "2_2") (pintype "passive"))
      (node (ref "R5") (pin "2") (pinfunction "2_2") (pintype "passive"))
      (node (ref "U1") (pin "2") (pinfunction "NEG_1_2") (pintype "input"))
      (node (ref "U3") (pin "6") (pinfunction "COM2_6") (pintype "bidirectional"))
    )
    (net (code "48") (name "Net-(U1-NEG_2)") (class "Default")
      (node (ref "R17") (pin "2") (pinfunction "2_2") (pintype "passive"))
      (node (ref "R19") (pin "2") (pinfunction "2_2") (pintype "passive"))
      (node (ref "R21") (pin "2") (pinfunction "2_2") (pintype "passive"))
      (node (ref "R23") (pin "2") (pinfunction "2_2") (pintype "passive"))
      (node (ref "R6") (pin "2") (pinfunction "2_2") (pintype "passive"))
      (node (ref "U1") (pin "6") (pinfunction "NEG_2_6") (pintype "input"))
      (node (ref "U3") (pin "2") (pinfunction "COM1_2") (pintype "bidirectional"))
    )
    (net (code "49") (name "Net-(U1-NEG_4)") (class "Default")
      (node (ref "R4") (pin "1") (pinfunction "1_1") (pintype "passive"))
      (node (ref "U1") (pin "13") (pinfunction "NEG_4_13") (pintype "input"))
      (node (ref "U1") (pin "14") (pinfunction "OUT4_14") (pintype "output"))
    )
    (net (code "50") (name "Net-(U1-OUT1)") (class "Default")
      (node (ref "C4") (pin "1") (pinfunction "1_1") (pintype "passive"))
      (node (ref "C6") (pin "1") (pinfunction "1_1") (pintype "passive"))
      (node (ref "C7") (pin "1") (pinfunction "1_1") (pintype "passive"))
      (node (ref "R5") (pin "1") (pinfunction "1_1") (pintype "passive"))
      (node (ref "U1") (pin "1") (pinfunction "OUT1_1") (pintype "output"))
      (node (ref "U1") (pin "10") (pinfunction "POS_3_10") (pintype "input"))
    )
    (net (code "51") (name "Net-(U1-OUT2)") (class "Default")
      (node (ref "C5") (pin "1") (pinfunction "1_1") (pintype "passive"))
      (node (ref "C8") (pin "1") (pinfunction "1_1") (pintype "passive"))
      (node (ref "C9") (pin "1") (pinfunction "1_1") (pintype "passive"))
      (node (ref "R6") (pin "1") (pinfunction "1_1") (pintype "passive"))
      (node (ref "U1") (pin "12") (pinfunction "POS_4_12") (pintype "input"))
      (node (ref "U1") (pin "7") (pinfunction "OUT2_7") (pintype "output"))
    )
    (net (code "52") (name "Net-(U1-POS_1)") (class "Default")
      (node (ref "C2") (pin "1") (pinfunction "1_1") (pintype "passive"))
      (node (ref "R7") (pin "2") (pinfunction "2_2") (pintype "passive"))
      (node (ref "R8") (pin "1") (pinfunction "1_1") (pintype "passive"))
      (node (ref "U1") (pin "3") (pinfunction "POS_1_3") (pintype "input"))
      (node (ref "U1") (pin "5") (pinfunction "POS_2_5") (pintype "input"))
    )
    (net (code "53") (name "Net-(U2-ADC6)") (class "Default")
      (node (ref "ADC6") (pin "TP") (pinfunction "TP_TP") (pintype "input"))
      (node (ref "U2") (pin "19") (pinfunction "ADC6_19") (pintype "input"))
    )
    (net (code "54") (name "Net-(U2-ADC7)") (class "Default")
      (node (ref "ADC7") (pin "TP") (pinfunction "TP_TP") (pintype "input"))
      (node (ref "U2") (pin "22") (pinfunction "ADC7_22") (pintype "input"))
    )
    (net (code "55") (name "Net-(U2-PB0)") (class "Default")
      (node (ref "U2") (pin "12") (pinfunction "PB0_12") (pintype "bidirectional"))
      (node (ref "VID") (pin "1") (pinfunction "P_1") (pintype "passive"))
    )
    (net (code "56") (name "Net-(U2-PB1)") (class "Default")
      (node (ref "R25") (pin "1") (pinfunction "1_1") (pintype "passive"))
      (node (ref "U2") (pin "13") (pinfunction "PB1_13") (pintype "bidirectional"))
    )
    (net (code "57") (name "Net-(U2-PB2)") (class "Default")
      (node (ref "R26") (pin "1") (pinfunction "1_1") (pintype "passive"))
      (node (ref "U2") (pin "14") (pinfunction "PB2_14") (pintype "bidirectional"))
    )
    (net (code "58") (name "Net-(U2-PB3)") (class "Default")
      (node (ref "JP1") (pin "4") (pinfunction "4_4") (pintype "passive"))
      (node (ref "R24") (pin "1") (pinfunction "1_1") (pintype "passive"))
      (node (ref "U2") (pin "15") (pinfunction "PB3_15") (pintype "bidirectional"))
    )
    (net (code "59") (name "Net-(U2-PB5)") (class "Default")
      (node (ref "JP1") (pin "3") (pinfunction "3_3") (pintype "passive"))
      (node (ref "PB5") (pin "TP") (pinfunction "TP_TP") (pintype "input"))
      (node (ref "R1") (pin "2") (pinfunction "2_2") (pintype "passive"))
      (node (ref "U2") (pin "17") (pinfunction "PB5_17") (pintype "bidirectional"))
    )
    (net (code "60") (name "Net-(U2-PC4)") (class "Default")
      (node (ref "PC4") (pin "TP") (pinfunction "TP_TP") (pintype "input"))
      (node (ref "U2") (pin "27") (pinfunction "PC4_27") (pintype "bidirectional"))
    )
    (net (code "61") (name "Net-(U2-PC5)") (class "Default")
      (node (ref "PC5") (pin "TP") (pinfunction "TP_TP") (pintype "input"))
      (node (ref "U2") (pin "28") (pinfunction "PC5_28") (pintype "bidirectional"))
    )
    (net (code "62") (name "Net-(U2-PC6)") (class "Default")
      (node (ref "JP1") (pin "5") (pinfunction "5_5") (pintype "passive"))
      (node (ref "R2") (pin "1") (pinfunction "1_1") (pintype "passive"))
      (node (ref "SV2") (pin "1") (pinfunction "1_1") (pintype "passive"))
      (node (ref "U2") (pin "29") (pinfunction "PC6_29") (pintype "bidirectional"))
    )
    (net (code "63") (name "Net-(U2-PD0)") (class "Default")
      (node (ref "SV2") (pin "2") (pinfunction "2_2") (pintype "passive"))
      (node (ref "U2") (pin "30") (pinfunction "PD0_30") (pintype "bidirectional"))
    )
    (net (code "64") (name "Net-(U2-PD1)") (class "Default")
      (node (ref "SV2") (pin "3") (pinfunction "3_3") (pintype "passive"))
      (node (ref "U2") (pin "31") (pinfunction "PD1_31") (pintype "bidirectional"))
    )
    (net (code "65") (name "Net-(U2-PD7)") (class "Default")
      (node (ref "U2") (pin "11") (pinfunction "PD7_11") (pintype "bidirectional"))
      (node (ref "U3") (pin "4") (pinfunction "IN1,IN2_4") (pintype "input"))
    )
    (net (code "66") (name "Net-(U3-NC1)") (class "Default")
      (node (ref "C8") (pin "2") (pinfunction "2_2") (pintype "passive"))
      (node (ref "U3") (pin "3") (pinfunction "NC1_3") (pintype "bidirectional"))
    )
    (net (code "67") (name "Net-(U3-NC2)") (class "Default")
      (node (ref "C7") (pin "2") (pinfunction "2_2") (pintype "passive"))
      (node (ref "U3") (pin "7") (pinfunction "NC2_7") (pintype "bidirectional"))
    )
    (net (code "68") (name "Net-(U3-NO1)") (class "Default")
      (node (ref "C9") (pin "2") (pinfunction "2_2") (pintype "passive"))
      (node (ref "U3") (pin "1") (pinfunction "NO1_1") (pintype "bidirectional"))
    )
    (net (code "69") (name "Net-(U3-NO2)") (class "Default")
      (node (ref "C6") (pin "2") (pinfunction "2_2") (pintype "passive"))
      (node (ref "U3") (pin "5") (pinfunction "NO2_5") (pintype "bidirectional"))
    )
    (net (code "70") (name "Net-(U4-CH.1IN)") (class "Default")
      (node (ref "C19") (pin "2") (pinfunction "2_2") (pintype "passive"))
      (node (ref "R29") (pin "1") (pinfunction "1_1") (pintype "passive"))
      (node (ref "U4") (pin "1") (pinfunction "CH.1IN_1") (pintype "input"))
    )
    (net (code "71") (name "Net-(U4-CH.2IN)") (class "Default")
      (node (ref "C20") (pin "2") (pinfunction "2_2") (pintype "passive"))
      (node (ref "R28") (pin "1") (pinfunction "1_1") (pintype "passive"))
      (node (ref "U4") (pin "2") (pinfunction "CH.2IN_2") (pintype "input"))
    )
    (net (code "72") (name "Net-(U4-CH.3IN)") (class "Default")
      (node (ref "C21") (pin "2") (pinfunction "2_2") (pintype "passive"))
      (node (ref "R27") (pin "1") (pinfunction "1_1") (pintype "passive"))
      (node (ref "U4") (pin "3") (pinfunction "CH.3IN_3") (pintype "input"))
    )
    (net (code "73") (name "Net-(YML-P)") (class "Default")
      (node (ref "C10") (pin "1") (pinfunction "1_1") (pintype "passive"))
      (node (ref "R9") (pin "1") (pinfunction "1_1") (pintype "passive"))
      (node (ref "YML") (pin "1") (pinfunction "P_1") (pintype "passive"))
    )
    (net (code "74") (name "Net-(YMR-P)") (class "Default")
      (node (ref "C17") (pin "1") (pinfunction "1_1") (pintype "passive"))
      (node (ref "R22") (pin "1") (pinfunction "1_1") (pintype "passive"))
      (node (ref "YMR") (pin "1") (pinfunction "P_1") (pintype "passive"))
    )
    (net (code "75") (name "unconnected-(U3-COM3-Pad10)") (class "Default")
      (node (ref "U3") (pin "10") (pinfunction "COM3_10") (pintype "bidirectional"))
    )
    (net (code "76") (name "unconnected-(U3-COM4-Pad14)") (class "Default")
      (node (ref "U3") (pin "14") (pinfunction "COM4_14") (pintype "bidirectional"))
    )
    (net (code "77") (name "unconnected-(U3-IN3,IN4-Pad12)") (class "Default")
      (node (ref "U3") (pin "12") (pinfunction "IN3,IN4_12") (pintype "input"))
    )
    (net (code "78") (name "unconnected-(U3-NC3-Pad11)") (class "Default")
      (node (ref "U3") (pin "11") (pinfunction "NC3_11") (pintype "bidirectional"))
    )
    (net (code "79") (name "unconnected-(U3-NC4-Pad15)") (class "Default")
      (node (ref "U3") (pin "15") (pinfunction "NC4_15") (pintype "bidirectional"))
    )
    (net (code "80") (name "unconnected-(U3-NO3-Pad9)") (class "Default")
      (node (ref "U3") (pin "9") (pinfunction "NO3_9") (pintype "bidirectional"))
    )
    (net (code "81") (name "unconnected-(U3-NO4-Pad13)") (class "Default")
      (node (ref "U3") (pin "13") (pinfunction "NO4_13") (pintype "bidirectional"))
    )
  )
)
